# Schematic.net
KiCad netlist of a schematic drawn in EAGLE
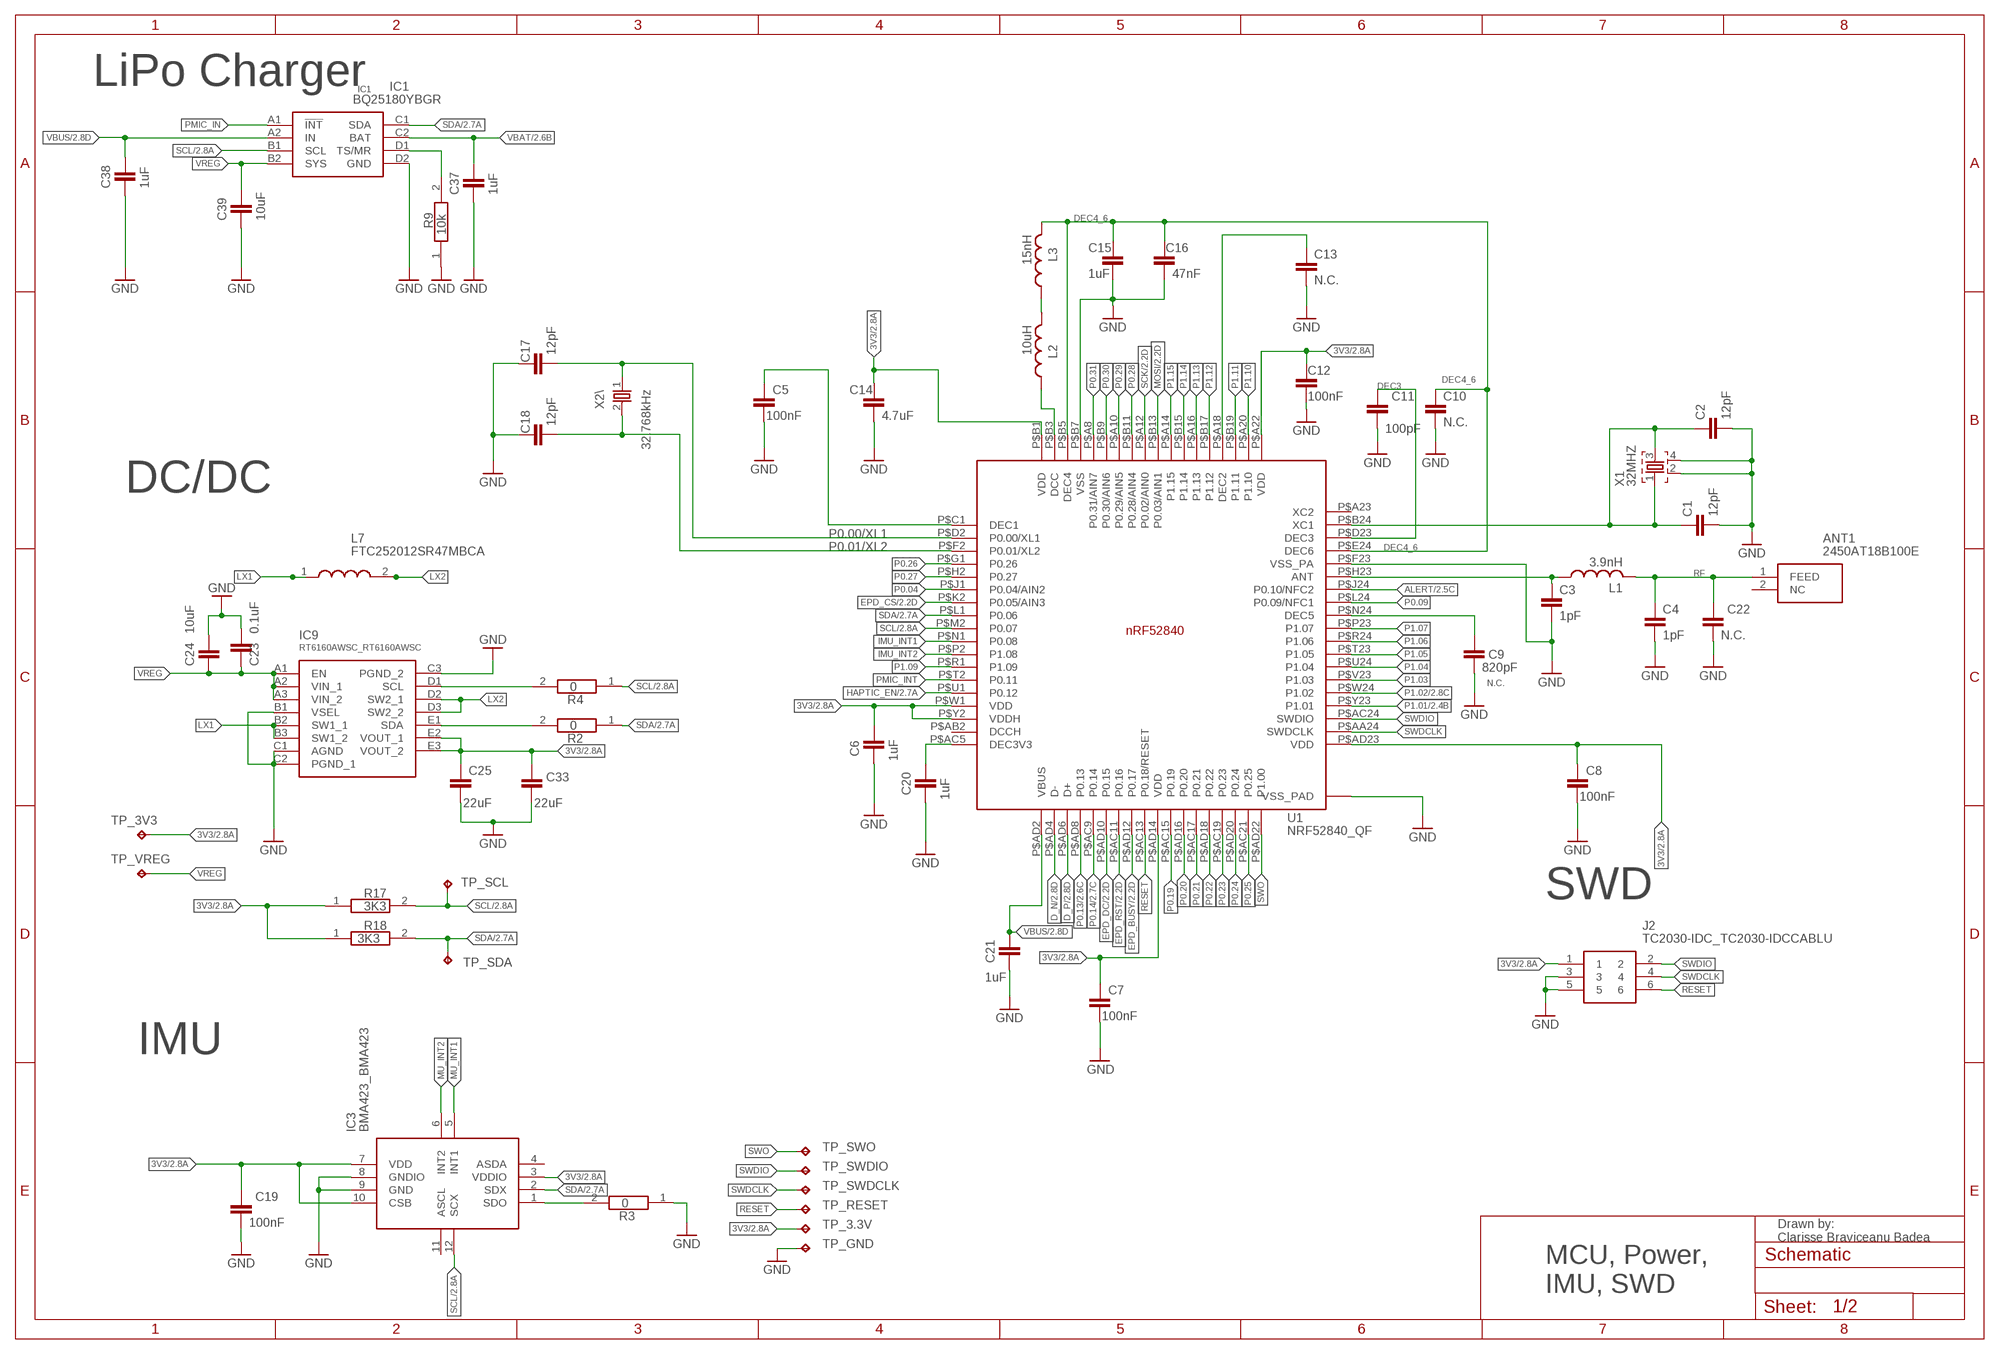
[diagram p0: schematic, sheet 1]
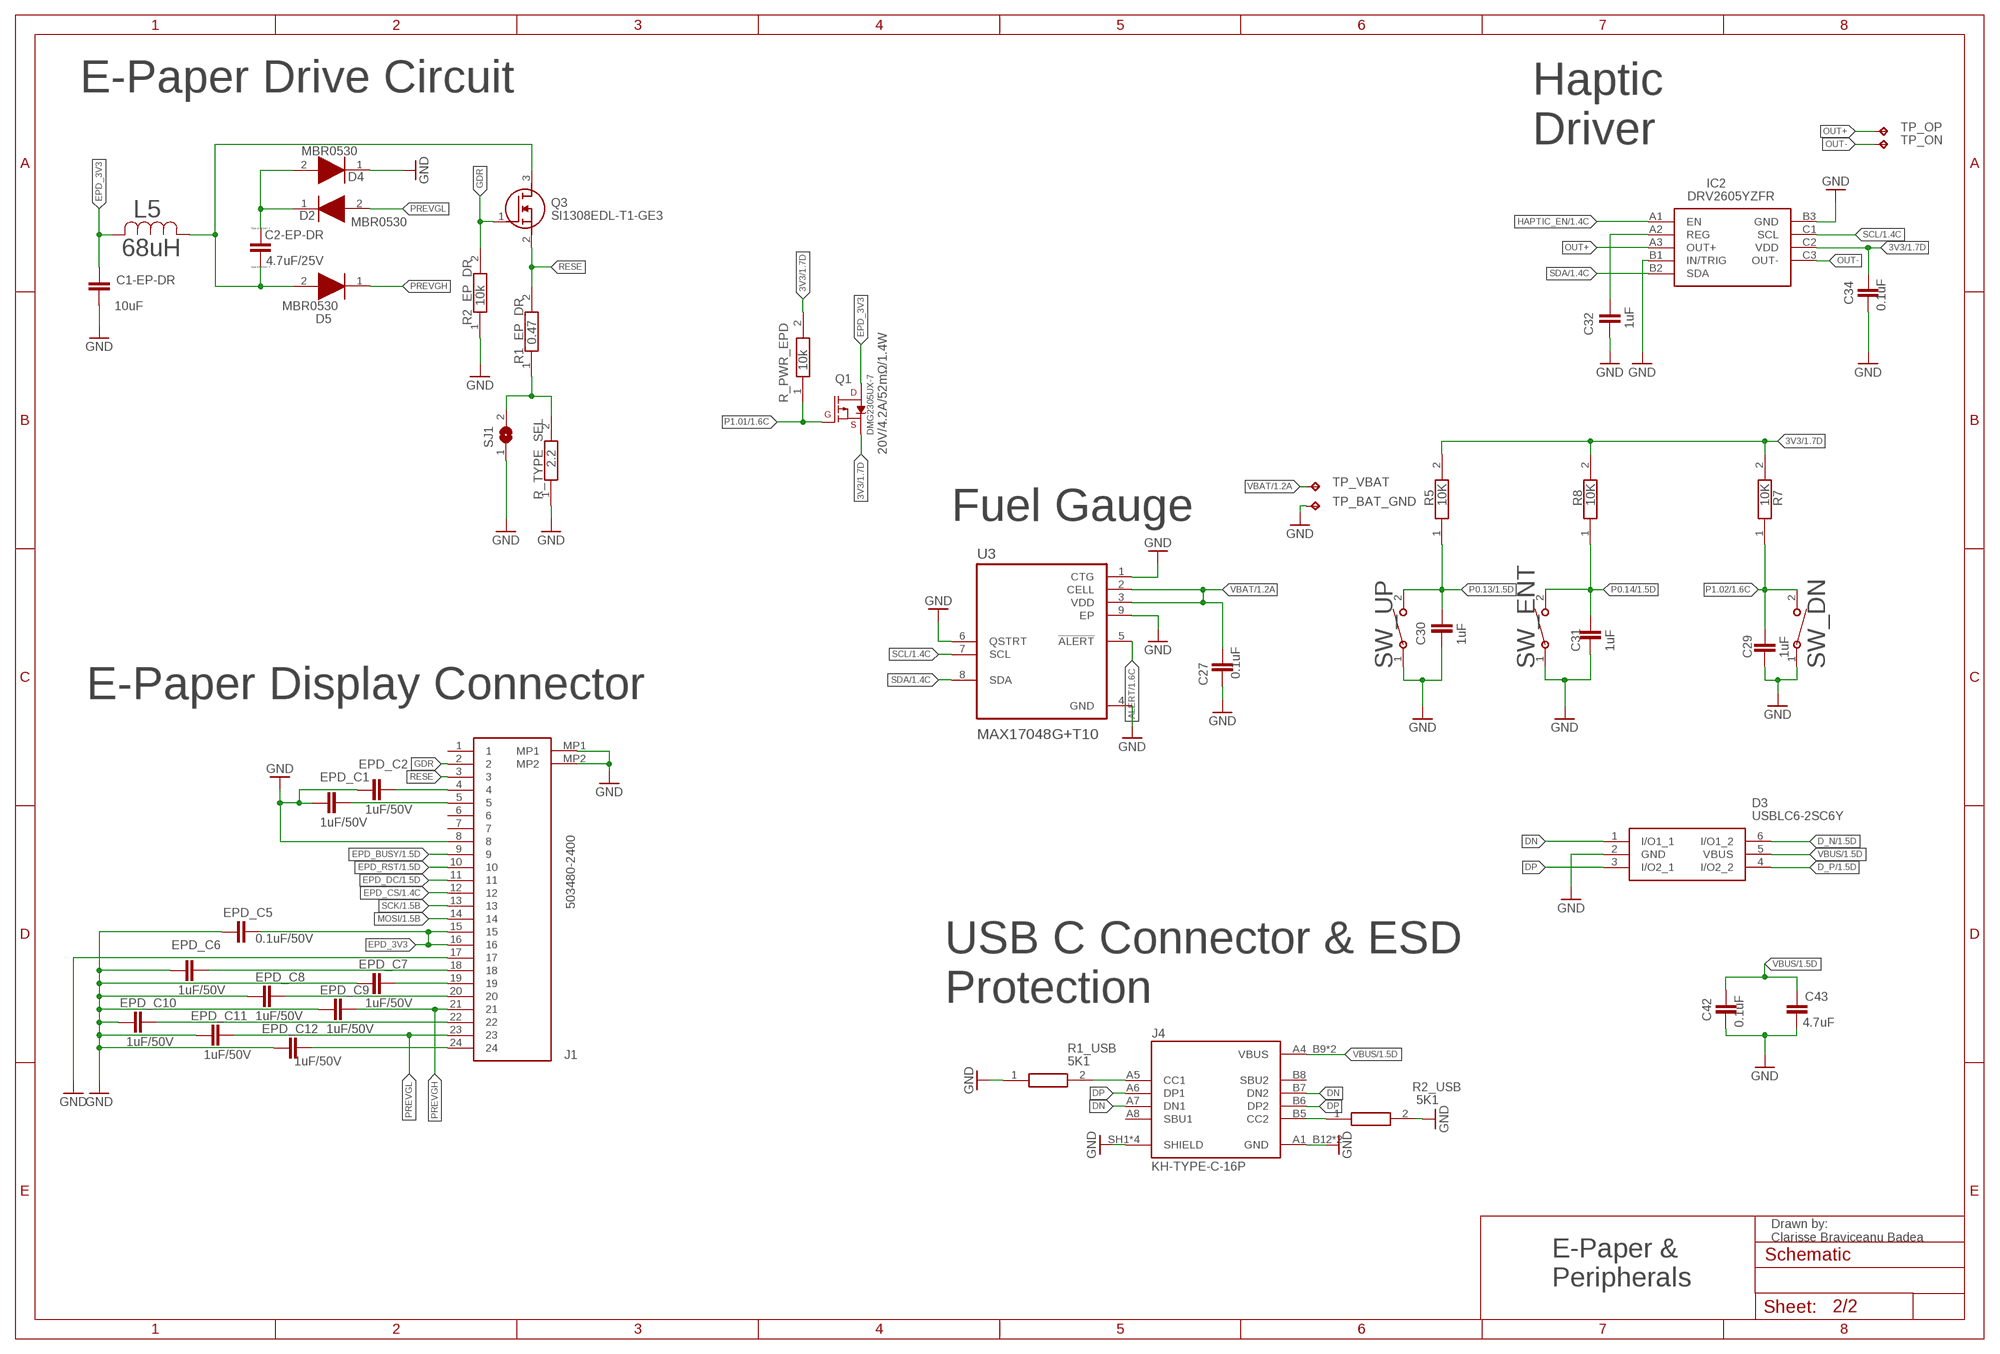
[diagram p1: schematic, sheet 2]

(export (version "E")
  (design (tool "Eeschema 10.0.6"))
  (components
    (comp (ref "ANT1")
      (value "2450AT18B100E")
      (footprint "eagle-import:2450AT18B100E_ANTC3216X140N")
      (fields (field (name "MOUSER_PART_NUMBER") "609-2450AT18B100E"))
      (libsource (lib "eagle-import") (part "2450AT18B100E_2450AT18B100E"))
    )
    (comp (ref "C1")
      (value "12pF")
      (footprint "eagle-import:NORDIC_NRF_3_RESC0201_N")
      (libsource (lib "eagle-import") (part "NORDIC_NRF_3_CAPACITOR_0201_N"))
    )
    (comp (ref "C2")
      (value "12pF")
      (footprint "eagle-import:NORDIC_NRF_3_RESC0201_N")
      (libsource (lib "eagle-import") (part "NORDIC_NRF_3_CAPACITOR_0201_N"))
    )
    (comp (ref "C3")
      (value "1pF")
      (footprint "eagle-import:NORDIC_NRF_3_RESC0201_N")
      (libsource (lib "eagle-import") (part "NORDIC_NRF_3_CAPACITOR_0201_N"))
    )
    (comp (ref "C4")
      (value "1pF")
      (footprint "eagle-import:NORDIC_NRF_3_RESC0201_N")
      (libsource (lib "eagle-import") (part "NORDIC_NRF_3_CAPACITOR_0201_N"))
    )
    (comp (ref "C5")
      (value "100nF")
      (footprint "eagle-import:NORDIC_NRF_3_RESC0201_N")
      (libsource (lib "eagle-import") (part "NORDIC_NRF_3_CAPACITOR_0201_N"))
    )
    (comp (ref "C6")
      (value "1uF")
      (footprint "eagle-import:NORDIC_NRF_3_RESC0402_N")
      (libsource (lib "eagle-import") (part "NORDIC_NRF_3_CAPACITOR_0402_N"))
    )
    (comp (ref "C7")
      (value "100nF")
      (footprint "eagle-import:NORDIC_NRF_3_RESC0201_N")
      (libsource (lib "eagle-import") (part "NORDIC_NRF_3_CAPACITOR_0201_N"))
    )
    (comp (ref "C8")
      (value "100nF")
      (footprint "eagle-import:NORDIC_NRF_3_RESC0201_N")
      (libsource (lib "eagle-import") (part "NORDIC_NRF_3_CAPACITOR_0201_N"))
    )
    (comp (ref "C9")
      (value "820pF")
      (footprint "eagle-import:NORDIC_NRF_3_RESC0201_N")
      (libsource (lib "eagle-import") (part "NORDIC_NRF_3_CAPACITOR_0201_N"))
    )
    (comp (ref "C10")
      (value "N.C.")
      (footprint "eagle-import:NORDIC_NRF_3_RESC0201_N")
      (libsource (lib "eagle-import") (part "NORDIC_NRF_3_CAPACITOR_0201_N"))
    )
    (comp (ref "C11")
      (value "100pF")
      (footprint "eagle-import:NORDIC_NRF_3_RESC0201_N")
      (libsource (lib "eagle-import") (part "NORDIC_NRF_3_CAPACITOR_0201_N"))
    )
    (comp (ref "C12")
      (value "100nF")
      (footprint "eagle-import:NORDIC_NRF_3_RESC0201_N")
      (libsource (lib "eagle-import") (part "NORDIC_NRF_3_CAPACITOR_0201_N"))
    )
    (comp (ref "C13")
      (value "N.C.")
      (footprint "eagle-import:NORDIC_NRF_3_RESC0201_N")
      (libsource (lib "eagle-import") (part "NORDIC_NRF_3_CAPACITOR_0201_N"))
    )
    (comp (ref "C14")
      (value "4.7uF")
      (footprint "eagle-import:NORDIC_NRF_3_RESC0402_N")
      (libsource (lib "eagle-import") (part "NORDIC_NRF_3_CAPACITOR_0402_N"))
    )
    (comp (ref "C15")
      (value "1uF")
      (footprint "eagle-import:NORDIC_NRF_3_RESC0402_N")
      (libsource (lib "eagle-import") (part "NORDIC_NRF_3_CAPACITOR_0402_N"))
    )
    (comp (ref "C16")
      (value "47nF")
      (footprint "eagle-import:NORDIC_NRF_3_RESC0201_N")
      (libsource (lib "eagle-import") (part "NORDIC_NRF_3_CAPACITOR_0201_N"))
    )
    (comp (ref "C17")
      (value "12pF")
      (footprint "eagle-import:NORDIC_NRF_3_RESC0201_N")
      (libsource (lib "eagle-import") (part "NORDIC_NRF_3_CAPACITOR_0201_N"))
    )
    (comp (ref "C18")
      (value "12pF")
      (footprint "eagle-import:NORDIC_NRF_3_RESC0201_N")
      (libsource (lib "eagle-import") (part "NORDIC_NRF_3_CAPACITOR_0201_N"))
    )
    (comp (ref "C19")
      (value "100nF")
      (footprint "eagle-import:NORDIC_NRF_3_RESC0201_N")
      (libsource (lib "eagle-import") (part "NORDIC_NRF_3_CAPACITOR_0201_N"))
    )
    (comp (ref "C20")
      (value "1uF")
      (footprint "eagle-import:NORDIC_NRF_3_RESC0402_N")
      (libsource (lib "eagle-import") (part "NORDIC_NRF_3_CAPACITOR_0402_N"))
    )
    (comp (ref "C21")
      (value "1uF")
      (footprint "eagle-import:NORDIC_NRF_3_RESC0402_N")
      (libsource (lib "eagle-import") (part "NORDIC_NRF_3_CAPACITOR_0402_N"))
    )
    (comp (ref "C22")
      (value "N.C.")
      (footprint "eagle-import:NORDIC_NRF_3_RESC0201_N")
      (libsource (lib "eagle-import") (part "NORDIC_NRF_3_CAPACITOR_0201_N"))
    )
    (comp (ref "C23")
      (value "0.1uF")
      (footprint "eagle-import:NORDIC_NRF_3_RESC0201_N")
      (libsource (lib "eagle-import") (part "NORDIC_NRF_3_CAPACITOR_0201_N"))
    )
    (comp (ref "C24")
      (value "10uF")
      (footprint "eagle-import:NORDIC_NRF_3_RESC0402_N")
      (libsource (lib "eagle-import") (part "NORDIC_NRF_3_CAPACITOR_0402_N"))
    )
    (comp (ref "C25")
      (value "22uF")
      (footprint "eagle-import:NORDIC_NRF_3_RESC0402_N")
      (libsource (lib "eagle-import") (part "NORDIC_NRF_3_CAPACITOR_0402_N"))
    )
    (comp (ref "C33")
      (value "22uF")
      (footprint "eagle-import:NORDIC_NRF_3_RESC0402_N")
      (libsource (lib "eagle-import") (part "NORDIC_NRF_3_CAPACITOR_0402_N"))
    )
    (comp (ref "C37")
      (value "1uF")
      (footprint "eagle-import:NORDIC_NRF_3_RESC0402_N")
      (libsource (lib "eagle-import") (part "NORDIC_NRF_3_CAPACITOR_0402_N"))
    )
    (comp (ref "C38")
      (value "1uF")
      (footprint "eagle-import:NORDIC_NRF_3_RESC0402_N")
      (libsource (lib "eagle-import") (part "NORDIC_NRF_3_CAPACITOR_0402_N"))
    )
    (comp (ref "C39")
      (value "10uF")
      (footprint "eagle-import:NORDIC_NRF_3_RESC0402_N")
      (libsource (lib "eagle-import") (part "NORDIC_NRF_3_CAPACITOR_0402_N"))
    )
    (comp (ref "IC1")
      (value "BQ25180YBGR")
      (footprint "eagle-import:BQ25180YBGR_BGA8C40P2X4_100X155X50")
      (fields (field (name "MOUSER_PART_NUMBER") "595-BQ25180YBGR"))
      (libsource (lib "eagle-import") (part "BQ25180YBGR_BQ25180YBGR"))
    )
    (comp (ref "IC3")
      (value "BMA423_BMA423")
      (footprint "eagle-import:BMA423_BMA423")
      (fields
        (field (name "MANUFACTURER_PART_NUMBER") "BMA423")
        (field (name "MOUSER_PART_NUMBER") "262-BMA423")
      )
      (libsource (lib "eagle-import") (part "BMA423_BMA423"))
    )
    (comp (ref "IC9")
      (value "RT6160AWSC_RT6160AWSC")
      (footprint "eagle-import:RT6160AWSC_BGA15C40P3X5_140X230X60")
      (fields
        (field (name "MANUFACTURER_PART_NUMBER") "RT6160AWSC")
        (field (name "MOUSER_PART_NUMBER") "835-RT6160AWSC")
      )
      (libsource (lib "eagle-import") (part "RT6160AWSC_RT6160AWSC"))
    )
    (comp (ref "J2")
      (value "TC2030-IDC_TC2030-IDCCABLU")
      (footprint "eagle-import:TC2030-IDC_TC2030IDC")
      (libsource (lib "eagle-import") (part "TC2030-IDC_TC2030-IDCCABLU"))
    )
    (comp (ref "L1")
      (value "3.9nH")
      (footprint "eagle-import:NORDIC_NRF_2_RESC0402_L")
      (libsource (lib "eagle-import") (part "NORDIC_NRF_2_INDUCTOR_0402_L"))
    )
    (comp (ref "L2")
      (value "10uH")
      (footprint "eagle-import:NORDIC_NRF_2_RESC0402_L")
      (libsource (lib "eagle-import") (part "NORDIC_NRF_2_INDUCTOR_0402_L"))
    )
    (comp (ref "L3")
      (value "15nH")
      (footprint "eagle-import:NORDIC_NRF_2_RESC0402_L")
      (libsource (lib "eagle-import") (part "NORDIC_NRF_2_INDUCTOR_0402_L"))
    )
    (comp (ref "L7")
      (value "FTC252012SR47MBCA")
      (footprint "eagle-import:MLP2016SR47MT0S1_INDC2016X100N")
      (libsource (lib "eagle-import") (part "MLP2016SR47MT0S1_FTC252012SR47MBCA"))
    )
    (comp (ref "R2")
      (value "0")
      (footprint "eagle-import:CPF0201D7K68C1_0201")
      (libsource (lib "eagle-import") (part "CPF0201D7K68C1_CPF0201D7K68C1"))
    )
    (comp (ref "R3")
      (value "0")
      (footprint "eagle-import:CPF0201D7K68C1_0201")
      (libsource (lib "eagle-import") (part "CPF0201D7K68C1_CPF0201D7K68C1"))
    )
    (comp (ref "R4")
      (value "0")
      (footprint "eagle-import:CPF0201D7K68C1_0201")
      (libsource (lib "eagle-import") (part "CPF0201D7K68C1_CPF0201D7K68C1"))
    )
    (comp (ref "R9")
      (value "10k")
      (footprint "eagle-import:CPF0201D7K68C1_0201")
      (libsource (lib "eagle-import") (part "CPF0201D7K68C1_CPF0201D7K68C1"))
    )
    (comp (ref "R17")
      (value "3K3")
      (footprint "eagle-import:CPF0201D7K68C1_0201")
      (libsource (lib "eagle-import") (part "CPF0201D7K68C1_CPF0201D7K68C1"))
    )
    (comp (ref "R18")
      (value "3K3")
      (footprint "eagle-import:CPF0201D7K68C1_0201")
      (libsource (lib "eagle-import") (part "CPF0201D7K68C1_CPF0201D7K68C1"))
    )
    (comp (ref "TP_3.3V")
      (value "HECTOR_WATCH_1_TPTP20R")
      (footprint "eagle-import:HECTOR_WATCH_1_TP20R")
      (libsource (lib "eagle-import") (part "HECTOR_WATCH_1_TPTP20R"))
    )
    (comp (ref "TP_3V3")
      (value "HECTOR_WATCH_1_TPTP20R")
      (footprint "eagle-import:HECTOR_WATCH_1_TP20R")
      (libsource (lib "eagle-import") (part "HECTOR_WATCH_1_TPTP20R"))
    )
    (comp (ref "TP_GND")
      (value "HECTOR_WATCH_1_TPTP20R")
      (footprint "eagle-import:HECTOR_WATCH_1_TP20R")
      (libsource (lib "eagle-import") (part "HECTOR_WATCH_1_TPTP20R"))
    )
    (comp (ref "TP_RESET")
      (value "HECTOR_WATCH_1_TPTP20R")
      (footprint "eagle-import:HECTOR_WATCH_1_TP20R")
      (libsource (lib "eagle-import") (part "HECTOR_WATCH_1_TPTP20R"))
    )
    (comp (ref "TP_SCL")
      (value "HECTOR_WATCH_1_TPTP20R")
      (footprint "eagle-import:HECTOR_WATCH_1_TP20R")
      (libsource (lib "eagle-import") (part "HECTOR_WATCH_1_TPTP20R"))
    )
    (comp (ref "TP_SDA")
      (value "HECTOR_WATCH_1_TPTP20R")
      (footprint "eagle-import:HECTOR_WATCH_1_TP20R")
      (libsource (lib "eagle-import") (part "HECTOR_WATCH_1_TPTP20R"))
    )
    (comp (ref "TP_SWDCLK")
      (value "HECTOR_WATCH_1_TPTP20R")
      (footprint "eagle-import:HECTOR_WATCH_1_TP20R")
      (libsource (lib "eagle-import") (part "HECTOR_WATCH_1_TPTP20R"))
    )
    (comp (ref "TP_SWDIO")
      (value "HECTOR_WATCH_1_TPTP20R")
      (footprint "eagle-import:HECTOR_WATCH_1_TP20R")
      (libsource (lib "eagle-import") (part "HECTOR_WATCH_1_TPTP20R"))
    )
    (comp (ref "TP_SWO")
      (value "HECTOR_WATCH_1_TPTP20R")
      (footprint "eagle-import:HECTOR_WATCH_1_TP20R")
      (libsource (lib "eagle-import") (part "HECTOR_WATCH_1_TPTP20R"))
    )
    (comp (ref "TP_VREG")
      (value "HECTOR_WATCH_1_TPTP20R")
      (footprint "eagle-import:HECTOR_WATCH_1_TP20R")
      (libsource (lib "eagle-import") (part "HECTOR_WATCH_1_TPTP20R"))
    )
    (comp (ref "U1")
      (value "NRF52840_QF")
      (footprint "eagle-import:NORDIC_NRF_4_AQFN50P700X700X85_HS-74N")
      (libsource (lib "eagle-import") (part "NORDIC_NRF_4_NRF52840_QF"))
    )
    (comp (ref "X1")
      (value "32MHZ")
      (footprint "eagle-import:NORDIC_NRF_BT-XTAL_2016_N")
      (libsource (lib "eagle-import") (part "NORDIC_NRF_XTAL_32MHZ"))
    )
    (comp (ref "X2\\")
      (value "32.768kHz")
      (footprint "eagle-import:NORDIC_NRF_1_XTAL_3215_N")
      (libsource (lib "eagle-import") (part "NORDIC_NRF_1_XTAL_32KHZ"))
    )
    (comp (ref "C1-EP-DR")
      (value "10uF")
      (footprint "eagle-import:NORDIC_NRF_3_RESC0402_N")
      (libsource (lib "eagle-import") (part "NORDIC_NRF_3_CAPACITOR_0402_N"))
    )
    (comp (ref "C2-EP-DR")
      (value "4.7uF/25V")
      (footprint "eagle-import:ESP32_C6_LIBRARY_1_ESP32_WROVER_EAGLE-LTSPICE_C0402")
      (libsource (lib "eagle-import") (part "ESP32_C6_LIBRARY_1_ESP32_WROVER_EAGLE-LTSPICE_CC0402"))
    )
    (comp (ref "C27")
      (value "0.1uF")
      (footprint "eagle-import:NORDIC_NRF_3_RESC0402_N")
      (libsource (lib "eagle-import") (part "NORDIC_NRF_3_CAPACITOR_0402_N"))
    )
    (comp (ref "C29")
      (value "1uF")
      (footprint "eagle-import:NORDIC_NRF_3_RESC0402_N")
      (libsource (lib "eagle-import") (part "NORDIC_NRF_3_CAPACITOR_0402_N"))
    )
    (comp (ref "C30")
      (value "1uF")
      (footprint "eagle-import:NORDIC_NRF_3_RESC0402_N")
      (libsource (lib "eagle-import") (part "NORDIC_NRF_3_CAPACITOR_0402_N"))
    )
    (comp (ref "C31")
      (value "1uF")
      (footprint "eagle-import:NORDIC_NRF_3_RESC0402_N")
      (libsource (lib "eagle-import") (part "NORDIC_NRF_3_CAPACITOR_0402_N"))
    )
    (comp (ref "C32")
      (value "1uF")
      (footprint "eagle-import:NORDIC_NRF_3_RESC0402_N")
      (libsource (lib "eagle-import") (part "NORDIC_NRF_3_CAPACITOR_0402_N"))
    )
    (comp (ref "C34")
      (value "0.1uF")
      (footprint "eagle-import:NORDIC_NRF_3_RESC0201_N")
      (libsource (lib "eagle-import") (part "NORDIC_NRF_3_CAPACITOR_0201_N"))
    )
    (comp (ref "C42")
      (value "0.1uF")
      (footprint "eagle-import:NORDIC_NRF_3_RESC0201_N")
      (libsource (lib "eagle-import") (part "NORDIC_NRF_3_CAPACITOR_0201_N"))
    )
    (comp (ref "C43")
      (value "4.7uF")
      (footprint "eagle-import:NORDIC_NRF_3_RESC0402_N")
      (libsource (lib "eagle-import") (part "NORDIC_NRF_3_CAPACITOR_0402_N"))
    )
    (comp (ref "D2")
      (value "MBR0530")
      (footprint "eagle-import:ESP32_C6_LIBRARY_5_SOD3716X135N")
      (fields (field (name "MF") "ON Semiconductor"))
      (libsource (lib "eagle-import") (part "ESP32_C6_LIBRARY_5_MBR0530"))
    )
    (comp (ref "D3")
      (value "USBLC6-2SC6Y")
      (footprint "eagle-import:ESP32_C6_LIBRARY_3_SOT95P280X145-6N")
      (fields (field (name "MF") "STMicroelectronics"))
      (libsource (lib "eagle-import") (part "ESP32_C6_LIBRARY_3_USBLC6-2SC6Y"))
    )
    (comp (ref "D4")
      (value "MBR0530")
      (footprint "eagle-import:ESP32_C6_LIBRARY_5_SOD3716X135N")
      (fields (field (name "MF") "ON Semiconductor"))
      (libsource (lib "eagle-import") (part "ESP32_C6_LIBRARY_5_MBR0530"))
    )
    (comp (ref "D5")
      (value "MBR0530")
      (footprint "eagle-import:ESP32_C6_LIBRARY_5_SOD3716X135N")
      (fields (field (name "MF") "ON Semiconductor"))
      (libsource (lib "eagle-import") (part "ESP32_C6_LIBRARY_5_MBR0530"))
    )
    (comp (ref "EPD_C1")
      (value "1uF/50V")
      (footprint "eagle-import:NORDIC_NRF_3_RESC0402_N")
      (libsource (lib "eagle-import") (part "NORDIC_NRF_3_CAPACITOR_0402_N"))
    )
    (comp (ref "EPD_C2")
      (value "1uF/50V")
      (footprint "eagle-import:NORDIC_NRF_3_RESC0402_N")
      (libsource (lib "eagle-import") (part "NORDIC_NRF_3_CAPACITOR_0402_N"))
    )
    (comp (ref "EPD_C5")
      (value "0.1uF/50V")
      (footprint "eagle-import:NORDIC_NRF_3_RESC0402_N")
      (libsource (lib "eagle-import") (part "NORDIC_NRF_3_CAPACITOR_0402_N"))
    )
    (comp (ref "EPD_C6")
      (value "1uF/50V")
      (footprint "eagle-import:NORDIC_NRF_3_RESC0402_N")
      (libsource (lib "eagle-import") (part "NORDIC_NRF_3_CAPACITOR_0402_N"))
    )
    (comp (ref "EPD_C7")
      (value "1uF/50V")
      (footprint "eagle-import:NORDIC_NRF_3_RESC0402_N")
      (libsource (lib "eagle-import") (part "NORDIC_NRF_3_CAPACITOR_0402_N"))
    )
    (comp (ref "EPD_C8")
      (value "1uF/50V")
      (footprint "eagle-import:NORDIC_NRF_3_RESC0402_N")
      (libsource (lib "eagle-import") (part "NORDIC_NRF_3_CAPACITOR_0402_N"))
    )
    (comp (ref "EPD_C9")
      (value "1uF/50V")
      (footprint "eagle-import:NORDIC_NRF_3_RESC0402_N")
      (libsource (lib "eagle-import") (part "NORDIC_NRF_3_CAPACITOR_0402_N"))
    )
    (comp (ref "EPD_C10")
      (value "1uF/50V")
      (footprint "eagle-import:NORDIC_NRF_3_RESC0402_N")
      (libsource (lib "eagle-import") (part "NORDIC_NRF_3_CAPACITOR_0402_N"))
    )
    (comp (ref "EPD_C11")
      (value "1uF/50V")
      (footprint "eagle-import:NORDIC_NRF_3_RESC0402_N")
      (libsource (lib "eagle-import") (part "NORDIC_NRF_3_CAPACITOR_0402_N"))
    )
    (comp (ref "EPD_C12")
      (value "1uF/50V")
      (footprint "eagle-import:NORDIC_NRF_3_RESC0402_N")
      (libsource (lib "eagle-import") (part "NORDIC_NRF_3_CAPACITOR_0402_N"))
    )
    (comp (ref "IC2")
      (value "DRV2605YZFR")
      (footprint "eagle-import:DRV2605YZFR_BGA9C50P3X3_144X144X62")
      (libsource (lib "eagle-import") (part "DRV2605YZFR_DRV2605YZFR"))
    )
    (comp (ref "J1")
      (value "503480-2400")
      (footprint "eagle-import:503480-2400_5034802400")
      (fields (field (name "MOUSER_PART_NUMBER") "538-503480-2400"))
      (libsource (lib "eagle-import") (part "503480-2400_503480-2400"))
    )
    (comp (ref "J4")
      (value "KH-TYPE-C-16P")
      (footprint "eagle-import:KH-TYPE-C-16P_KINGHELM_KH-TYPE-C-16P")
      (fields (field (name "MF") "kinghelm"))
      (libsource (lib "eagle-import") (part "KH-TYPE-C-16P_KH-TYPE-C-16P"))
    )
    (comp (ref "L5")
      (value "68uH")
      (footprint "eagle-import:ESP32_C6_LIBRARY_2_IND_4828-WE-TPC_WRE")
      (fields
        (field (name "MANUFACTURER_PART_NUMBER") "744043680")
        (field (name "COPYRIGHT") "Copyright (C) 2024 Ultra Librarian. All rights reserved.")
      )
      (libsource (lib "eagle-import") (part "ESP32_C6_LIBRARY_2_744043680IND_4828-WE-TPC_WRE"))
    )
    (comp (ref "Q1")
      (value "20V/4.2A/52mΩ/1.4W")
      (footprint "eagle-import:ESP32_C6_LIBRARY_4_ESP32_C6_LIBRARY_4_ESP32_C6_LIBRARY_4_ESP32_C6_LIBRARY_4_ESP32_WROVER_SPARKFUN-DISCRETESEMI_SOT23-3")
      (libsource (lib "eagle-import") (part "ESP32_C6_LIBRARY_4_ESP32_WROVER_SPARKFUN-DISCRETESEMI_MOSFET_PCH-DMG2305UX-7"))
    )
    (comp (ref "Q3")
      (value "SI1308EDL-T1-GE3")
      (footprint "eagle-import:ESP32_C6_LIBRARY_6_SOT65P210X110-3N")
      (fields (field (name "MF") "Vishay Siliconix"))
      (libsource (lib "eagle-import") (part "ESP32_C6_LIBRARY_6_SI1308EDL-T1-GE3"))
    )
    (comp (ref "R1_EP_DR")
      (value "0.47")
      (footprint "eagle-import:CPF0201D7K68C1_0201")
      (libsource (lib "eagle-import") (part "CPF0201D7K68C1_CPF0201D7K68C1"))
    )
    (comp (ref "R1_USB")
      (value "5K1")
      (footprint "eagle-import:CPF0201D7K68C1_0201")
      (libsource (lib "eagle-import") (part "CPF0201D7K68C1_CPF0201D7K68C1"))
    )
    (comp (ref "R2_EP_DR")
      (value "10k")
      (footprint "eagle-import:CPF0201D7K68C1_0201")
      (libsource (lib "eagle-import") (part "CPF0201D7K68C1_CPF0201D7K68C1"))
    )
    (comp (ref "R2_USB")
      (value "5K1")
      (footprint "eagle-import:CPF0201D7K68C1_0201")
      (libsource (lib "eagle-import") (part "CPF0201D7K68C1_CPF0201D7K68C1"))
    )
    (comp (ref "R5")
      (value "10K")
      (footprint "eagle-import:CPF0201D7K68C1_0201")
      (libsource (lib "eagle-import") (part "CPF0201D7K68C1_CPF0201D7K68C1"))
    )
    (comp (ref "R7")
      (value "10K")
      (footprint "eagle-import:CPF0201D7K68C1_0201")
      (libsource (lib "eagle-import") (part "CPF0201D7K68C1_CPF0201D7K68C1"))
    )
    (comp (ref "R8")
      (value "10K")
      (footprint "eagle-import:CPF0201D7K68C1_0201")
      (libsource (lib "eagle-import") (part "CPF0201D7K68C1_CPF0201D7K68C1"))
    )
    (comp (ref "R_PWR_EPD")
      (value "10k")
      (footprint "eagle-import:CPF0201D7K68C1_0201")
      (libsource (lib "eagle-import") (part "CPF0201D7K68C1_CPF0201D7K68C1"))
    )
    (comp (ref "R_TYPE_SEL")
      (value "2.2")
      (footprint "eagle-import:CPF0201D7K68C1_0201")
      (libsource (lib "eagle-import") (part "CPF0201D7K68C1_CPF0201D7K68C1"))
    )
    (comp (ref "SJ1")
      (value "ESP32_C6_LIBRARY_7_JUMPER_SJ")
      (footprint "eagle-import:ESP32_C6_LIBRARY_7_JUMPER_SJ")
      (libsource (lib "eagle-import") (part "ESP32_C6_LIBRARY_7_JUMPER_SJ"))
    )
    (comp (ref "SW_DN")
      (value "2025-10-22_07-23-44_LIBRARY_EVP-AKE31ASW_EVP-AKE31A_PAN")
      (footprint "eagle-import:2025-10-22_07-23-44_LIBRARY_SW_EVP-AKE31A_PAN")
      (libsource (lib "eagle-import") (part "2025-10-22_07-23-44_LIBRARY_EVP-AKE31ASW_EVP-AKE31A_PAN"))
    )
    (comp (ref "SW_ENT")
      (value "2025-10-22_07-23-44_LIBRARY_EVP-AKE31ASW_EVP-AKE31A_PAN")
      (footprint "eagle-import:2025-10-22_07-23-44_LIBRARY_SW_EVP-AKE31A_PAN")
      (libsource (lib "eagle-import") (part "2025-10-22_07-23-44_LIBRARY_EVP-AKE31ASW_EVP-AKE31A_PAN"))
    )
    (comp (ref "SW_UP")
      (value "2025-10-22_07-23-44_LIBRARY_EVP-AKE31ASW_EVP-AKE31A_PAN")
      (footprint "eagle-import:2025-10-22_07-23-44_LIBRARY_SW_EVP-AKE31A_PAN")
      (libsource (lib "eagle-import") (part "2025-10-22_07-23-44_LIBRARY_EVP-AKE31ASW_EVP-AKE31A_PAN"))
    )
    (comp (ref "TP_BAT_GND")
      (value "HECTOR_WATCH_1_TPTP20R")
      (footprint "eagle-import:HECTOR_WATCH_1_TP20R")
      (libsource (lib "eagle-import") (part "HECTOR_WATCH_1_TPTP20R"))
    )
    (comp (ref "TP_ON")
      (value "HECTOR_WATCH_1_TPTP20R")
      (footprint "eagle-import:HECTOR_WATCH_1_TP20R")
      (libsource (lib "eagle-import") (part "HECTOR_WATCH_1_TPTP20R"))
    )
    (comp (ref "TP_OP")
      (value "HECTOR_WATCH_1_TPTP20R")
      (footprint "eagle-import:HECTOR_WATCH_1_TP20R")
      (libsource (lib "eagle-import") (part "HECTOR_WATCH_1_TPTP20R"))
    )
    (comp (ref "TP_VBAT")
      (value "HECTOR_WATCH_1_TPTP20R")
      (footprint "eagle-import:HECTOR_WATCH_1_TP20R")
      (libsource (lib "eagle-import") (part "HECTOR_WATCH_1_TPTP20R"))
    )
    (comp (ref "U3")
      (value "MAX17048G+T10")
      (footprint "eagle-import:ESP32_C6_LIBRARY_SON50P200X200X80-9N")
      (libsource (lib "eagle-import") (part "ESP32_C6_LIBRARY_MAX17048G+T10CC"))
    )
  )
  (nets
    (net (code "1") (name "3V3") (class "Default")
      (node (ref "C12") (pin "2") (pinfunction "2_2") (pintype "passive"))
      (node (ref "C14") (pin "1") (pinfunction "1_1") (pintype "passive"))
      (node (ref "C19") (pin "2") (pinfunction "2_2") (pintype "passive"))
      (node (ref "C25") (pin "1") (pinfunction "1_1") (pintype "passive"))
      (node (ref "C33") (pin "1") (pinfunction "1_1") (pintype "passive"))
      (node (ref "C34") (pin "1") (pinfunction "1_1") (pintype "passive"))
      (node (ref "C6") (pin "1") (pinfunction "1_1") (pintype "passive"))
      (node (ref "C7") (pin "1") (pinfunction "1_1") (pintype "passive"))
      (node (ref "C8") (pin "1") (pinfunction "1_1") (pintype "passive"))
      (node (ref "IC2") (pin "C2") (pinfunction "VDD_C2") (pintype "bidirectional"))
      (node (ref "IC3") (pin "10") (pinfunction "CSB_10") (pintype "bidirectional"))
      (node (ref "IC3") (pin "3") (pinfunction "VDDIO_3") (pintype "bidirectional"))
      (node (ref "IC3") (pin "7") (pinfunction "VDD_7") (pintype "bidirectional"))
      (node (ref "IC9") (pin "E2") (pinfunction "VOUT_1_E2") (pintype "bidirectional"))
      (node (ref "IC9") (pin "E3") (pinfunction "VOUT_2_E3") (pintype "bidirectional"))
      (node (ref "J2") (pin "1") (pinfunction "1_1") (pintype "bidirectional"))
      (node (ref "Q1") (pin "2") (pinfunction "S_2") (pintype "bidirectional"))
      (node (ref "R17") (pin "1") (pinfunction "1_1") (pintype "bidirectional"))
      (node (ref "R18") (pin "1") (pinfunction "1_1") (pintype "bidirectional"))
      (node (ref "R5") (pin "2") (pinfunction "2_2") (pintype "bidirectional"))
      (node (ref "R7") (pin "2") (pinfunction "2_2") (pintype "bidirectional"))
      (node (ref "R8") (pin "2") (pinfunction "2_2") (pintype "bidirectional"))
      (node (ref "R_PWR_EPD") (pin "2") (pinfunction "2_2") (pintype "bidirectional"))
      (node (ref "TP_3.3V") (pin "TP") (pinfunction "TP_TP") (pintype "input"))
      (node (ref "TP_3V3") (pin "TP") (pinfunction "TP_TP") (pintype "input"))
      (node (ref "U1") (pin "P$A22") (pinfunction "VDD_P$A22") (pintype "power_in"))
      (node (ref "U1") (pin "P$AD14") (pinfunction "VDD_P$AD14") (pintype "power_in"))
      (node (ref "U1") (pin "P$AD23") (pinfunction "VDD_P$AD23") (pintype "power_in"))
      (node (ref "U1") (pin "P$B1") (pinfunction "VDD_P$B1") (pintype "power_in"))
      (node (ref "U1") (pin "P$W1") (pinfunction "VDD_P$W1") (pintype "power_in"))
      (node (ref "U1") (pin "P$Y2") (pinfunction "VDDH_P$Y2") (pintype "power_in"))
    )
    (net (code "2") (name "ALERT") (class "Default")
      (node (ref "U1") (pin "P$J24") (pinfunction "P0.10/NFC2_P$J24") (pintype "bidirectional"))
      (node (ref "U3") (pin "5") (pinfunction "~{ALERT}_5") (pintype "output"))
    )
    (net (code "3") (name "DN") (class "Default")
      (node (ref "D3") (pin "1") (pinfunction "I/O1_1_1") (pintype "bidirectional"))
      (node (ref "J4") (pin "A7") (pinfunction "DN1_A7") (pintype "bidirectional"))
      (node (ref "J4") (pin "B7") (pinfunction "DN2_B7") (pintype "bidirectional"))
    )
    (net (code "4") (name "DP") (class "Default")
      (node (ref "D3") (pin "3") (pinfunction "I/O2_1_3") (pintype "bidirectional"))
      (node (ref "J4") (pin "A6") (pinfunction "DP1_A6") (pintype "bidirectional"))
      (node (ref "J4") (pin "B6") (pinfunction "DP2_B6") (pintype "bidirectional"))
    )
    (net (code "5") (name "D_N") (class "Default")
      (node (ref "D3") (pin "6") (pinfunction "I/O1_2_6") (pintype "bidirectional"))
      (node (ref "U1") (pin "P$AD4") (pinfunction "D-_P$AD4") (pintype "bidirectional"))
    )
    (net (code "6") (name "D_P") (class "Default")
      (node (ref "D3") (pin "4") (pinfunction "I/O2_2_4") (pintype "bidirectional"))
      (node (ref "U1") (pin "P$AD6") (pinfunction "D+_P$AD6") (pintype "bidirectional"))
    )
    (net (code "7") (name "EPD_3V3") (class "Default")
      (node (ref "C1-EP-DR") (pin "1") (pinfunction "1_1") (pintype "passive"))
      (node (ref "EPD_C5") (pin "2") (pinfunction "2_2") (pintype "passive"))
      (node (ref "J1") (pin "15") (pinfunction "15_15") (pintype "bidirectional"))
      (node (ref "J1") (pin "16") (pinfunction "16_16") (pintype "bidirectional"))
      (node (ref "L5") (pin "2") (pinfunction "2_2") (pintype "passive"))
      (node (ref "Q1") (pin "3") (pinfunction "D_3") (pintype "bidirectional"))
    )
    (net (code "8") (name "EPD_BUSY") (class "Default")
      (node (ref "J1") (pin "9") (pinfunction "9_9") (pintype "bidirectional"))
      (node (ref "U1") (pin "P$AD12") (pinfunction "P0.17_P$AD12") (pintype "bidirectional"))
    )
    (net (code "9") (name "EPD_CS") (class "Default")
      (node (ref "J1") (pin "12") (pinfunction "12_12") (pintype "bidirectional"))
      (node (ref "U1") (pin "P$K2") (pinfunction "P0.05/AIN3_P$K2") (pintype "bidirectional"))
    )
    (net (code "10") (name "EPD_DC") (class "Default")
      (node (ref "J1") (pin "11") (pinfunction "11_11") (pintype "bidirectional"))
      (node (ref "U1") (pin "P$AD10") (pinfunction "P0.15_P$AD10") (pintype "bidirectional"))
    )
    (net (code "11") (name "EPD_RST") (class "Default")
      (node (ref "J1") (pin "10") (pinfunction "10_10") (pintype "bidirectional"))
      (node (ref "U1") (pin "P$AC11") (pinfunction "P0.16_P$AC11") (pintype "bidirectional"))
    )
    (net (code "12") (name "GDR") (class "Default")
      (node (ref "J1") (pin "2") (pinfunction "2_2") (pintype "bidirectional"))
      (node (ref "Q3") (pin "1") (pinfunction "G_1") (pintype "bidirectional"))
      (node (ref "R2_EP_DR") (pin "2") (pinfunction "2_2") (pintype "bidirectional"))
    )
    (net (code "13") (name "GND") (class "Default")
      (node (ref "C1") (pin "2") (pinfunction "2_2") (pintype "passive"))
      (node (ref "C1-EP-DR") (pin "2") (pinfunction "2_2") (pintype "passive"))
      (node (ref "C10") (pin "1") (pinfunction "1_1") (pintype "passive"))
      (node (ref "C11") (pin "1") (pinfunction "1_1") (pintype "passive"))
      (node (ref "C12") (pin "1") (pinfunction "1_1") (pintype "passive"))
      (node (ref "C13") (pin "1") (pinfunction "1_1") (pintype "passive"))
      (node (ref "C14") (pin "2") (pinfunction "2_2") (pintype "passive"))
      (node (ref "C15") (pin "2") (pinfunction "2_2") (pintype "passive"))
      (node (ref "C16") (pin "1") (pinfunction "1_1") (pintype "passive"))
      (node (ref "C17") (pin "1") (pinfunction "1_1") (pintype "passive"))
      (node (ref "C18") (pin "1") (pinfunction "1_1") (pintype "passive"))
      (node (ref "C19") (pin "1") (pinfunction "1_1") (pintype "passive"))
      (node (ref "C2") (pin "2") (pinfunction "2_2") (pintype "passive"))
      (node (ref "C20") (pin "2") (pinfunction "2_2") (pintype "passive"))
      (node (ref "C21") (pin "2") (pinfunction "2_2") (pintype "passive"))
      (node (ref "C22") (pin "1") (pinfunction "1_1") (pintype "passive"))
      (node (ref "C23") (pin "1") (pinfunction "1_1") (pintype "passive"))
      (node (ref "C24") (pin "1") (pinfunction "1_1") (pintype "passive"))
      (node (ref "C25") (pin "2") (pinfunction "2_2") (pintype "passive"))
      (node (ref "C27") (pin "1") (pinfunction "1_1") (pintype "passive"))
      (node (ref "C29") (pin "2") (pinfunction "2_2") (pintype "passive"))
      (node (ref "C3") (pin "1") (pinfunction "1_1") (pintype "passive"))
      (node (ref "C30") (pin "1") (pinfunction "1_1") (pintype "passive"))
      (node (ref "C31") (pin "1") (pinfunction "1_1") (pintype "passive"))
      (node (ref "C32") (pin "1") (pinfunction "1_1") (pintype "passive"))
      (node (ref "C33") (pin "2") (pinfunction "2_2") (pintype "passive"))
      (node (ref "C34") (pin "2") (pinfunction "2_2") (pintype "passive"))
      (node (ref "C37") (pin "2") (pinfunction "2_2") (pintype "passive"))
      (node (ref "C38") (pin "2") (pinfunction "2_2") (pintype "passive"))
      (node (ref "C39") (pin "2") (pinfunction "2_2") (pintype "passive"))
      (node (ref "C4") (pin "1") (pinfunction "1_1") (pintype "passive"))
      (node (ref "C42") (pin "2") (pinfunction "2_2") (pintype "passive"))
      (node (ref "C43") (pin "2") (pinfunction "2_2") (pintype "passive"))
      (node (ref "C5") (pin "2") (pinfunction "2_2") (pintype "passive"))
      (node (ref "C6") (pin "2") (pinfunction "2_2") (pintype "passive"))
      (node (ref "C7") (pin "2") (pinfunction "2_2") (pintype "passive"))
      (node (ref "C8") (pin "2") (pinfunction "2_2") (pintype "passive"))
      (node (ref "C9") (pin "1") (pinfunction "1_1") (pintype "passive"))
      (node (ref "D3") (pin "2") (pinfunction "GND_2") (pintype "bidirectional"))
      (node (ref "D4") (pin "1") (pinfunction "K_1") (pintype "bidirectional"))
      (node (ref "EPD_C1") (pin "1") (pinfunction "1_1") (pintype "passive"))
      (node (ref "EPD_C10") (pin "1") (pinfunction "1_1") (pintype "passive"))
      (node (ref "EPD_C11") (pin "1") (pinfunction "1_1") (pintype "passive"))
      (node (ref "EPD_C12") (pin "1") (pinfunction "1_1") (pintype "passive"))
      (node (ref "EPD_C2") (pin "1") (pinfunction "1_1") (pintype "passive"))
      (node (ref "EPD_C5") (pin "1") (pinfunction "1_1") (pintype "passive"))
      (node (ref "EPD_C6") (pin "1") (pinfunction "1_1") (pintype "passive"))
      (node (ref "EPD_C7") (pin "1") (pinfunction "1_1") (pintype "passive"))
      (node (ref "EPD_C8") (pin "1") (pinfunction "1_1") (pintype "passive"))
      (node (ref "EPD_C9") (pin "1") (pinfunction "1_1") (pintype "passive"))
      (node (ref "IC1") (pin "D2") (pinfunction "GND_D2") (pintype "bidirectional"))
      (node (ref "IC2") (pin "B1") (pinfunction "IN/TRIG_B1") (pintype "bidirectional"))
      (node (ref "IC2") (pin "B3") (pinfunction "GND_B3") (pintype "bidirectional"))
      (node (ref "IC3") (pin "8") (pinfunction "GNDIO_8") (pintype "bidirectional"))
      (node (ref "IC3") (pin "9") (pinfunction "GND_9") (pintype "bidirectional"))
      (node (ref "IC9") (pin "B1") (pinfunction "VSEL_B1") (pintype "bidirectional"))
      (node (ref "IC9") (pin "C1") (pinfunction "AGND_C1") (pintype "bidirectional"))
      (node (ref "IC9") (pin "C2") (pinfunction "PGND_1_C2") (pintype "bidirectional"))
      (node (ref "IC9") (pin "C3") (pinfunction "PGND_2_C3") (pintype "bidirectional"))
      (node (ref "J1") (pin "17") (pinfunction "17_17") (pintype "bidirectional"))
      (node (ref "J1") (pin "8") (pinfunction "8_8") (pintype "bidirectional"))
      (node (ref "J1") (pin "MP1") (pinfunction "MP1_MP1") (pintype "bidirectional"))
      (node (ref "J1") (pin "MP2") (pinfunction "MP2_MP2") (pintype "bidirectional"))
      (node (ref "J2") (pin "3") (pinfunction "3_3") (pintype "bidirectional"))
      (node (ref "J2") (pin "5") (pinfunction "5_5") (pintype "bidirectional"))
      (node (ref "J4") (pin "A12_B1") (pinfunction "GND_A12_B1") (pintype "power_in"))
      (node (ref "J4") (pin "A1_B12") (pinfunction "GND_A1_B12") (pintype "power_in"))
      (node (ref "J4") (pin "SH1") (pinfunction "SHIELD_SH1") (pintype "passive"))
      (node (ref "J4") (pin "SH2") (pinfunction "SHIELD_SH2") (pintype "passive"))
      (node (ref "J4") (pin "SH3") (pinfunction "SHIELD_SH3") (pintype "passive"))
      (node (ref "J4") (pin "SH4") (pinfunction "SHIELD_SH4") (pintype "passive"))
      (node (ref "R1_USB") (pin "1") (pinfunction "1_1") (pintype "bidirectional"))
      (node (ref "R2_EP_DR") (pin "1") (pinfunction "1_1") (pintype "bidirectional"))
      (node (ref "R2_USB") (pin "2") (pinfunction "2_2") (pintype "bidirectional"))
      (node (ref "R3") (pin "1") (pinfunction "1_1") (pintype "bidirectional"))
      (node (ref "R9") (pin "1") (pinfunction "1_1") (pintype "bidirectional"))
      (node (ref "R_TYPE_SEL") (pin "1") (pinfunction "1_1") (pintype "bidirectional"))
      (node (ref "SJ1") (pin "1") (pinfunction "1_1") (pintype "passive"))
      (node (ref "SW_DN") (pin "1") (pinfunction "1_1") (pintype "passive"))
      (node (ref "SW_ENT") (pin "1") (pinfunction "1_1") (pintype "passive"))
      (node (ref "SW_UP") (pin "1") (pinfunction "1_1") (pintype "passive"))
      (node (ref "TP_BAT_GND") (pin "TP") (pinfunction "TP_TP") (pintype "input"))
      (node (ref "TP_GND") (pin "TP") (pinfunction "TP_TP") (pintype "input"))
      (node (ref "U1") (pin "P$74") (pinfunction "VSS_PAD_P$74") (pintype "bidirectional"))
      (node (ref "U1") (pin "P$75") (pinfunction "VSS_PAD_P$75") (pintype "bidirectional"))
      (node (ref "U1") (pin "P$76") (pinfunction "VSS_PAD_P$76") (pintype "bidirectional"))
      (node (ref "U1") (pin "P$77") (pinfunction "VSS_PAD_P$77") (pintype "bidirectional"))
      (node (ref "U1") (pin "P$78") (pinfunction "VSS_PAD_P$78") (pintype "bidirectional"))
      (node (ref "U1") (pin "P$79") (pinfunction "VSS_PAD_P$79") (pintype "bidirectional"))
      (node (ref "U1") (pin "P$80") (pinfunction "VSS_PAD_P$80") (pintype "bidirectional"))
      (node (ref "U1") (pin "P$81") (pinfunction "VSS_PAD_P$81") (pintype "bidirectional"))
      (node (ref "U1") (pin "P$82") (pinfunction "VSS_PAD_P$82") (pintype "bidirectional"))
      (node (ref "U1") (pin "P$83") (pinfunction "VSS_PAD_P$83") (pintype "bidirectional"))
      (node (ref "U1") (pin "P$84") (pinfunction "VSS_PAD_P$84") (pintype "bidirectional"))
      (node (ref "U1") (pin "P$85") (pinfunction "VSS_PAD_P$85") (pintype "bidirectional"))
      (node (ref "U1") (pin "P$86") (pinfunction "VSS_PAD_P$86") (pintype "bidirectional"))
      (node (ref "U1") (pin "P$87") (pinfunction "VSS_PAD_P$87") (pintype "bidirectional"))
      (node (ref "U1") (pin "P$88") (pinfunction "VSS_PAD_P$88") (pintype "bidirectional"))
      (node (ref "U1") (pin "P$89") (pinfunction "VSS_PAD_P$89") (pintype "bidirectional"))
      (node (ref "U1") (pin "P$90") (pinfunction "VSS_PAD_P$90") (pintype "bidirectional"))
      (node (ref "U1") (pin "P$B7") (pinfunction "VSS_P$B7") (pintype "power_in"))
      (node (ref "U1") (pin "P$F23") (pinfunction "VSS_PA_P$F23") (pintype "bidirectional"))
      (node (ref "U3") (pin "1") (pinfunction "CTG_1") (pintype "power_in"))
      (node (ref "U3") (pin "4") (pinfunction "GND_4") (pintype "power_in"))
      (node (ref "U3") (pin "6") (pinfunction "QSTRT_6") (pintype "input"))
      (node (ref "U3") (pin "9") (pinfunction "EP_9") (pintype "power_in"))
      (node (ref "X1") (pin "2") (pinfunction "2_2") (pintype "passive"))
      (node (ref "X1") (pin "4") (pinfunction "4_4") (pintype "passive"))
    )
    (net (code "14") (name "HAPTIC_EN") (class "Default")
      (node (ref "IC2") (pin "A1") (pinfunction "EN_A1") (pintype "bidirectional"))
      (node (ref "U1") (pin "P$U1") (pinfunction "P0.12_P$U1") (pintype "bidirectional"))
    )
    (net (code "15") (name "IMU_INT1") (class "Default")
      (node (ref "U1") (pin "P$N1") (pinfunction "P0.08_P$N1") (pintype "bidirectional"))
    )
    (net (code "16") (name "IMU_INT2") (class "Default")
      (node (ref "U1") (pin "P$P2") (pinfunction "P1.08_P$P2") (pintype "bidirectional"))
    )
    (net (code "17") (name "LX1") (class "Default")
      (node (ref "IC9") (pin "B2") (pinfunction "SW1_1_B2") (pintype "bidirectional"))
      (node (ref "IC9") (pin "B3") (pinfunction "SW1_2_B3") (pintype "bidirectional"))
      (node (ref "L7") (pin "1") (pinfunction "1_1") (pintype "bidirectional"))
    )
    (net (code "18") (name "LX2") (class "Default")
      (node (ref "IC9") (pin "D2") (pinfunction "SW2_1_D2") (pintype "bidirectional"))
      (node (ref "IC9") (pin "D3") (pinfunction "SW2_2_D3") (pintype "bidirectional"))
      (node (ref "L7") (pin "2") (pinfunction "2_2") (pintype "bidirectional"))
    )
    (net (code "19") (name "MOSI") (class "Default")
      (node (ref "J1") (pin "14") (pinfunction "14_14") (pintype "bidirectional"))
      (node (ref "U1") (pin "P$B13") (pinfunction "P0.03/AIN1_P$B13") (pintype "bidirectional"))
    )
    (net (code "20") (name "MU_INT1") (class "Default")
      (node (ref "IC3") (pin "5") (pinfunction "INT1_5") (pintype "bidirectional"))
    )
    (net (code "21") (name "MU_INT2") (class "Default")
      (node (ref "IC3") (pin "6") (pinfunction "INT2_6") (pintype "bidirectional"))
    )
    (net (code "22") (name "Net-(ANT1-FEED)") (class "Default")
      (node (ref "ANT1") (pin "1") (pinfunction "FEED_1") (pintype "input"))
      (node (ref "C22") (pin "2") (pinfunction "2_2") (pintype "passive"))
      (node (ref "C4") (pin "2") (pinfunction "2_2") (pintype "passive"))
      (node (ref "L1") (pin "2") (pinfunction "2_2") (pintype "passive"))
    )
    (net (code "23") (name "Net-(D2-K)") (class "Default")
      (node (ref "C2-EP-DR") (pin "1") (pinfunction "1_1") (pintype "passive"))
      (node (ref "D2") (pin "1") (pinfunction "K_1") (pintype "bidirectional"))
      (node (ref "D4") (pin "2") (pinfunction "A_2") (pintype "bidirectional"))
    )
    (net (code "24") (name "Net-(D5-A)") (class "Default")
      (node (ref "C2-EP-DR") (pin "2") (pinfunction "2_2") (pintype "passive"))
      (node (ref "D5") (pin "2") (pinfunction "A_2") (pintype "bidirectional"))
      (node (ref "L5") (pin "1") (pinfunction "1_1") (pintype "passive"))
      (node (ref "Q3") (pin "3") (pinfunction "D_3") (pintype "bidirectional"))
    )
    (net (code "25") (name "Net-(EPD_C1-Pad2)") (class "Default")
      (node (ref "EPD_C1") (pin "2") (pinfunction "2_2") (pintype "passive"))
      (node (ref "J1") (pin "5") (pinfunction "5_5") (pintype "bidirectional"))
    )
    (net (code "26") (name "Net-(EPD_C2-Pad2)") (class "Default")
      (node (ref "EPD_C2") (pin "2") (pinfunction "2_2") (pintype "passive"))
      (node (ref "J1") (pin "4") (pinfunction "4_4") (pintype "bidirectional"))
    )
    (net (code "27") (name "Net-(EPD_C6-Pad2)") (class "Default")
      (node (ref "EPD_C6") (pin "2") (pinfunction "2_2") (pintype "passive"))
      (node (ref "J1") (pin "18") (pinfunction "18_18") (pintype "bidirectional"))
    )
    (net (code "28") (name "Net-(EPD_C7-Pad2)") (class "Default")
      (node (ref "EPD_C7") (pin "2") (pinfunction "2_2") (pintype "passive"))
      (node (ref "J1") (pin "19") (pinfunction "19_19") (pintype "bidirectional"))
    )
    (net (code "29") (name "Net-(EPD_C8-Pad2)") (class "Default")
      (node (ref "EPD_C8") (pin "2") (pinfunction "2_2") (pintype "passive"))
      (node (ref "J1") (pin "20") (pinfunction "20_20") (pintype "bidirectional"))
    )
    (net (code "30") (name "Net-(EPD_C10-Pad2)") (class "Default")
      (node (ref "EPD_C10") (pin "2") (pinfunction "2_2") (pintype "passive"))
      (node (ref "J1") (pin "22") (pinfunction "22_22") (pintype "bidirectional"))
    )
    (net (code "31") (name "Net-(EPD_C12-Pad2)") (class "Default")
      (node (ref "EPD_C12") (pin "2") (pinfunction "2_2") (pintype "passive"))
      (node (ref "J1") (pin "24") (pinfunction "24_24") (pintype "bidirectional"))
    )
    (net (code "32") (name "Net-(IC1-TS{slash}MR)") (class "Default")
      (node (ref "IC1") (pin "D1") (pinfunction "TS/MR_D1") (pintype "bidirectional"))
      (node (ref "R9") (pin "2") (pinfunction "2_2") (pintype "bidirectional"))
    )
    (net (code "33") (name "Net-(IC2-REG)") (class "Default")
      (node (ref "C32") (pin "2") (pinfunction "2_2") (pintype "passive"))
      (node (ref "IC2") (pin "A2") (pinfunction "REG_A2") (pintype "bidirectional"))
    )
    (net (code "34") (name "Net-(IC3-SDO)") (class "Default")
      (node (ref "IC3") (pin "1") (pinfunction "SDO_1") (pintype "bidirectional"))
      (node (ref "R3") (pin "2") (pinfunction "2_2") (pintype "bidirectional"))
    )
    (net (code "35") (name "Net-(IC9-SCL)") (class "Default")
      (node (ref "IC9") (pin "D1") (pinfunction "SCL_D1") (pintype "bidirectional"))
      (node (ref "R4") (pin "2") (pinfunction "2_2") (pintype "bidirectional"))
    )
    (net (code "36") (name "Net-(IC9-SDA)") (class "Default")
      (node (ref "IC9") (pin "E1") (pinfunction "SDA_E1") (pintype "bidirectional"))
      (node (ref "R2") (pin "2") (pinfunction "2_2") (pintype "bidirectional"))
    )
    (net (code "37") (name "Net-(J4-CC1)") (class "Default")
      (node (ref "J4") (pin "A5") (pinfunction "CC1_A5") (pintype "bidirectional"))
      (node (ref "R1_USB") (pin "2") (pinfunction "2_2") (pintype "bidirectional"))
    )
    (net (code "38") (name "Net-(J4-CC2)") (class "Default")
      (node (ref "J4") (pin "B5") (pinfunction "CC2_B5") (pintype "bidirectional"))
      (node (ref "R2_USB") (pin "1") (pinfunction "1_1") (pintype "bidirectional"))
    )
    (net (code "39") (name "Net-(L2-Pad2)") (class "Default")
      (node (ref "L2") (pin "2") (pinfunction "2_2") (pintype "passive"))
      (node (ref "L3") (pin "1") (pinfunction "1_1") (pintype "passive"))
    )
    (net (code "40") (name "Net-(R1_EP_DR-Pad1)") (class "Default")
      (node (ref "R1_EP_DR") (pin "1") (pinfunction "1_1") (pintype "bidirectional"))
      (node (ref "R_TYPE_SEL") (pin "2") (pinfunction "2_2") (pintype "bidirectional"))
      (node (ref "SJ1") (pin "2") (pinfunction "2_2") (pintype "passive"))
    )
    (net (code "41") (name "Net-(U1-ANT)") (class "Default")
      (node (ref "C3") (pin "2") (pinfunction "2_2") (pintype "passive"))
      (node (ref "L1") (pin "1") (pinfunction "1_1") (pintype "passive"))
      (node (ref "U1") (pin "P$H23") (pinfunction "ANT_P$H23") (pintype "bidirectional"))
    )
    (net (code "42") (name "Net-(U1-DCC)") (class "Default")
      (node (ref "L2") (pin "1") (pinfunction "1_1") (pintype "passive"))
      (node (ref "U1") (pin "P$B3") (pinfunction "DCC_P$B3") (pintype "output"))
    )
    (net (code "43") (name "Net-(U1-DEC1)") (class "Default")
      (node (ref "C5") (pin "1") (pinfunction "1_1") (pintype "passive"))
      (node (ref "U1") (pin "P$C1") (pinfunction "DEC1_P$C1") (pintype "power_in"))
    )
    (net (code "44") (name "Net-(U1-DEC2)") (class "Default")
      (node (ref "C13") (pin "2") (pinfunction "2_2") (pintype "passive"))
      (node (ref "U1") (pin "P$A18") (pinfunction "DEC2_P$A18") (pintype "bidirectional"))
    )
    (net (code "45") (name "Net-(U1-DEC3)") (class "Default")
      (node (ref "C11") (pin "2") (pinfunction "2_2") (pintype "passive"))
      (node (ref "U1") (pin "P$D23") (pinfunction "DEC3_P$D23") (pintype "bidirectional"))
    )
    (net (code "46") (name "Net-(U1-DEC3V3)") (class "Default")
      (node (ref "C20") (pin "1") (pinfunction "1_1") (pintype "passive"))
      (node (ref "U1") (pin "P$AC5") (pinfunction "DEC3V3_P$AC5") (pintype "bidirectional"))
    )
    (net (code "47") (name "Net-(U1-DEC4)") (class "Default")
      (node (ref "C10") (pin "2") (pinfunction "2_2") (pintype "passive"))
      (node (ref "C15") (pin "1") (pinfunction "1_1") (pintype "passive"))
      (node (ref "C16") (pin "2") (pinfunction "2_2") (pintype "passive"))
      (node (ref "L3") (pin "2") (pinfunction "2_2") (pintype "passive"))
      (node (ref "U1") (pin "P$B5") (pinfunction "DEC4_P$B5") (pintype "power_in"))
      (node (ref "U1") (pin "P$E24") (pinfunction "DEC6_P$E24") (pintype "bidirectional"))
    )
    (net (code "48") (name "Net-(U1-DEC5)") (class "Default")
      (node (ref "C9") (pin "2") (pinfunction "2_2") (pintype "passive"))
      (node (ref "U1") (pin "P$N24") (pinfunction "DEC5_P$N24") (pintype "bidirectional"))
    )
    (net (code "49") (name "Net-(U1-P0.00{slash}XL1)") (class "Default")
      (node (ref "C17") (pin "2") (pinfunction "2_2") (pintype "passive"))
      (node (ref "U1") (pin "P$D2") (pinfunction "P0.00/XL1_P$D2") (pintype "bidirectional"))
      (node (ref "X2\\") (pin "1") (pinfunction "1_1") (pintype "passive"))
    )
    (net (code "50") (name "Net-(U1-P0.01{slash}XL2)") (class "Default")
      (node (ref "C18") (pin "2") (pinfunction "2_2") (pintype "passive"))
      (node (ref "U1") (pin "P$F2") (pinfunction "P0.01/XL2_P$F2") (pintype "bidirectional"))
      (node (ref "X2\\") (pin "2") (pinfunction "2_2") (pintype "passive"))
    )
    (net (code "51") (name "Net-(U1-XC1)") (class "Default")
      (node (ref "C1") (pin "1") (pinfunction "1_1") (pintype "passive"))
      (node (ref "C2") (pin "1") (pinfunction "1_1") (pintype "passive"))
      (node (ref "U1") (pin "P$B24") (pinfunction "XC1_P$B24") (pintype "input"))
      (node (ref "X1") (pin "1") (pinfunction "1_1") (pintype "passive"))
      (node (ref "X1") (pin "3") (pinfunction "3_3") (pintype "passive"))
    )
    (net (code "52") (name "OUT+") (class "Default")
      (node (ref "IC2") (pin "A3") (pinfunction "OUT+_A3") (pintype "bidirectional"))
      (node (ref "TP_OP") (pin "TP") (pinfunction "TP_TP") (pintype "input"))
    )
    (net (code "53") (name "OUT-") (class "Default")
      (node (ref "IC2") (pin "C3") (pinfunction "OUT-_C3") (pintype "bidirectional"))
      (node (ref "TP_ON") (pin "TP") (pinfunction "TP_TP") (pintype "input"))
    )
    (net (code "54") (name "P0.04") (class "Default")
      (node (ref "U1") (pin "P$J1") (pinfunction "P0.04/AIN2_P$J1") (pintype "bidirectional"))
    )
    (net (code "55") (name "P0.09") (class "Default")
      (node (ref "U1") (pin "P$L24") (pinfunction "P0.09/NFC1_P$L24") (pintype "bidirectional"))
    )
    (net (code "56") (name "P0.13") (class "Default")
      (node (ref "C30") (pin "2") (pinfunction "2_2") (pintype "passive"))
      (node (ref "R5") (pin "1") (pinfunction "1_1") (pintype "bidirectional"))
      (node (ref "SW_UP") (pin "2") (pinfunction "2_2") (pintype "passive"))
      (node (ref "U1") (pin "P$AD8") (pinfunction "P0.13_P$AD8") (pintype "bidirectional"))
    )
    (net (code "57") (name "P0.14") (class "Default")
      (node (ref "C31") (pin "2") (pinfunction "2_2") (pintype "passive"))
      (node (ref "R8") (pin "1") (pinfunction "1_1") (pintype "bidirectional"))
      (node (ref "SW_ENT") (pin "2") (pinfunction "2_2") (pintype "passive"))
      (node (ref "U1") (pin "P$AC9") (pinfunction "P0.14_P$AC9") (pintype "bidirectional"))
    )
    (net (code "58") (name "P0.19") (class "Default")
      (node (ref "U1") (pin "P$AC15") (pinfunction "P0.19_P$AC15") (pintype "bidirectional"))
    )
    (net (code "59") (name "P0.20") (class "Default")
      (node (ref "U1") (pin "P$AD16") (pinfunction "P0.20_P$AD16") (pintype "bidirectional"))
    )
    (net (code "60") (name "P0.21") (class "Default")
      (node (ref "U1") (pin "P$AC17") (pinfunction "P0.21_P$AC17") (pintype "bidirectional"))
    )
    (net (code "61") (name "P0.22") (class "Default")
      (node (ref "U1") (pin "P$AD18") (pinfunction "P0.22_P$AD18") (pintype "bidirectional"))
    )
    (net (code "62") (name "P0.23") (class "Default")
      (node (ref "U1") (pin "P$AC19") (pinfunction "P0.23_P$AC19") (pintype "bidirectional"))
    )
    (net (code "63") (name "P0.24") (class "Default")
      (node (ref "U1") (pin "P$AD20") (pinfunction "P0.24_P$AD20") (pintype "bidirectional"))
    )
    (net (code "64") (name "P0.25") (class "Default")
      (node (ref "U1") (pin "P$AC21") (pinfunction "P0.25_P$AC21") (pintype "bidirectional"))
    )
    (net (code "65") (name "P0.26") (class "Default")
      (node (ref "U1") (pin "P$G1") (pinfunction "P0.26_P$G1") (pintype "bidirectional"))
    )
    (net (code "66") (name "P0.27") (class "Default")
      (node (ref "U1") (pin "P$H2") (pinfunction "P0.27_P$H2") (pintype "bidirectional"))
    )
    (net (code "67") (name "P0.28") (class "Default")
      (node (ref "U1") (pin "P$B11") (pinfunction "P0.28/AIN4_P$B11") (pintype "bidirectional"))
    )
    (net (code "68") (name "P0.29") (class "Default")
      (node (ref "U1") (pin "P$A10") (pinfunction "P0.29/AIN5_P$A10") (pintype "bidirectional"))
    )
    (net (code "69") (name "P0.30") (class "Default")
      (node (ref "U1") (pin "P$B9") (pinfunction "P0.30/AIN6_P$B9") (pintype "bidirectional"))
    )
    (net (code "70") (name "P0.31") (class "Default")
      (node (ref "U1") (pin "P$A8") (pinfunction "P0.31/AIN7_P$A8") (pintype "bidirectional"))
    )
    (net (code "71") (name "P1.01") (class "Default")
      (node (ref "Q1") (pin "1") (pinfunction "G_1") (pintype "bidirectional"))
      (node (ref "R_PWR_EPD") (pin "1") (pinfunction "1_1") (pintype "bidirectional"))
      (node (ref "U1") (pin "P$Y23") (pinfunction "P1.01_P$Y23") (pintype "bidirectional"))
    )
    (net (code "72") (name "P1.02") (class "Default")
      (node (ref "C29") (pin "1") (pinfunction "1_1") (pintype "passive"))
      (node (ref "R7") (pin "1") (pinfunction "1_1") (pintype "bidirectional"))
      (node (ref "SW_DN") (pin "2") (pinfunction "2_2") (pintype "passive"))
      (node (ref "U1") (pin "P$W24") (pinfunction "P1.02_P$W24") (pintype "bidirectional"))
    )
    (net (code "73") (name "P1.03") (class "Default")
      (node (ref "U1") (pin "P$V23") (pinfunction "P1.03_P$V23") (pintype "bidirectional"))
    )
    (net (code "74") (name "P1.04") (class "Default")
      (node (ref "U1") (pin "P$U24") (pinfunction "P1.04_P$U24") (pintype "bidirectional"))
    )
    (net (code "75") (name "P1.05") (class "Default")
      (node (ref "U1") (pin "P$T23") (pinfunction "P1.05_P$T23") (pintype "bidirectional"))
    )
    (net (code "76") (name "P1.06") (class "Default")
      (node (ref "U1") (pin "P$R24") (pinfunction "P1.06_P$R24") (pintype "bidirectional"))
    )
    (net (code "77") (name "P1.07") (class "Default")
      (node (ref "U1") (pin "P$P23") (pinfunction "P1.07_P$P23") (pintype "bidirectional"))
    )
    (net (code "78") (name "P1.09") (class "Default")
      (node (ref "U1") (pin "P$R1") (pinfunction "P1.09_P$R1") (pintype "bidirectional"))
    )
    (net (code "79") (name "P1.10") (class "Default")
      (node (ref "U1") (pin "P$A20") (pinfunction "P1.10_P$A20") (pintype "bidirectional"))
    )
    (net (code "80") (name "P1.11") (class "Default")
      (node (ref "U1") (pin "P$B19") (pinfunction "P1.11_P$B19") (pintype "bidirectional"))
    )
    (net (code "81") (name "P1.12") (class "Default")
      (node (ref "U1") (pin "P$B17") (pinfunction "P1.12_P$B17") (pintype "bidirectional"))
    )
    (net (code "82") (name "P1.13") (class "Default")
      (node (ref "U1") (pin "P$A16") (pinfunction "P1.13_P$A16") (pintype "bidirectional"))
    )
    (net (code "83") (name "P1.14") (class "Default")
      (node (ref "U1") (pin "P$B15") (pinfunction "P1.14_P$B15") (pintype "bidirectional"))
    )
    (net (code "84") (name "P1.15") (class "Default")
      (node (ref "U1") (pin "P$A14") (pinfunction "P1.15_P$A14") (pintype "bidirectional"))
    )
    (net (code "85") (name "PMIC_IN") (class "Default")
      (node (ref "IC1") (pin "A1") (pinfunction "~{INT}_A1") (pintype "bidirectional"))
    )
    (net (code "86") (name "PMIC_INT") (class "Default")
      (node (ref "U1") (pin "P$T2") (pinfunction "P0.11_P$T2") (pintype "bidirectional"))
    )
    (net (code "87") (name "PREVGH") (class "Default")
      (node (ref "D5") (pin "1") (pinfunction "K_1") (pintype "bidirectional"))
      (node (ref "EPD_C9") (pin "2") (pinfunction "2_2") (pintype "passive"))
      (node (ref "J1") (pin "21") (pinfunction "21_21") (pintype "bidirectional"))
    )
    (net (code "88") (name "PREVGL") (class "Default")
      (node (ref "D2") (pin "2") (pinfunction "A_2") (pintype "bidirectional"))
      (node (ref "EPD_C11") (pin "2") (pinfunction "2_2") (pintype "passive"))
      (node (ref "J1") (pin "23") (pinfunction "23_23") (pintype "bidirectional"))
    )
    (net (code "89") (name "RESE") (class "Default")
      (node (ref "J1") (pin "3") (pinfunction "3_3") (pintype "bidirectional"))
      (node (ref "Q3") (pin "2") (pinfunction "S_2") (pintype "bidirectional"))
      (node (ref "R1_EP_DR") (pin "2") (pinfunction "2_2") (pintype "bidirectional"))
    )
    (net (code "90") (name "RESET") (class "Default")
      (node (ref "J2") (pin "6") (pinfunction "6_6") (pintype "bidirectional"))
      (node (ref "TP_RESET") (pin "TP") (pinfunction "TP_TP") (pintype "input"))
      (node (ref "U1") (pin "P$AC13") (pinfunction "P0.18/RESET_P$AC13") (pintype "bidirectional"))
    )
    (net (code "91") (name "SCK") (class "Default")
      (node (ref "J1") (pin "13") (pinfunction "13_13") (pintype "bidirectional"))
      (node (ref "U1") (pin "P$A12") (pinfunction "P0.02/AIN0_P$A12") (pintype "bidirectional"))
    )
    (net (code "92") (name "SCL") (class "Default")
      (node (ref "IC1") (pin "B1") (pinfunction "SCL_B1") (pintype "bidirectional"))
      (node (ref "IC2") (pin "C1") (pinfunction "SCL_C1") (pintype "bidirectional"))
      (node (ref "IC3") (pin "12") (pinfunction "SCX_12") (pintype "bidirectional"))
      (node (ref "R17") (pin "2") (pinfunction "2_2") (pintype "bidirectional"))
      (node (ref "R4") (pin "1") (pinfunction "1_1") (pintype "bidirectional"))
      (node (ref "TP_SCL") (pin "TP") (pinfunction "TP_TP") (pintype "input"))
      (node (ref "U1") (pin "P$M2") (pinfunction "P0.07_P$M2") (pintype "bidirectional"))
      (node (ref "U3") (pin "7") (pinfunction "SCL_7") (pintype "input"))
    )
    (net (code "93") (name "SDA") (class "Default")
      (node (ref "IC1") (pin "C1") (pinfunction "SDA_C1") (pintype "bidirectional"))
      (node (ref "IC2") (pin "B2") (pinfunction "SDA_B2") (pintype "bidirectional"))
      (node (ref "IC3") (pin "2") (pinfunction "SDX_2") (pintype "bidirectional"))
      (node (ref "R18") (pin "2") (pinfunction "2_2") (pintype "bidirectional"))
      (node (ref "R2") (pin "1") (pinfunction "1_1") (pintype "bidirectional"))
      (node (ref "TP_SDA") (pin "TP") (pinfunction "TP_TP") (pintype "input"))
      (node (ref "U1") (pin "P$L1") (pinfunction "P0.06_P$L1") (pintype "bidirectional"))
      (node (ref "U3") (pin "8") (pinfunction "SDA_8") (pintype "bidirectional"))
    )
    (net (code "94") (name "SWDCLK") (class "Default")
      (node (ref "J2") (pin "4") (pinfunction "4_4") (pintype "bidirectional"))
      (node (ref "TP_SWDCLK") (pin "TP") (pinfunction "TP_TP") (pintype "input"))
      (node (ref "U1") (pin "P$AA24") (pinfunction "SWDCLK_P$AA24") (pintype "input"))
    )
    (net (code "95") (name "SWDIO") (class "Default")
      (node (ref "J2") (pin "2") (pinfunction "2_2") (pintype "bidirectional"))
      (node (ref "TP_SWDIO") (pin "TP") (pinfunction "TP_TP") (pintype "input"))
      (node (ref "U1") (pin "P$AC24") (pinfunction "SWDIO_P$AC24") (pintype "bidirectional"))
    )
    (net (code "96") (name "SWO") (class "Default")
      (node (ref "TP_SWO") (pin "TP") (pinfunction "TP_TP") (pintype "input"))
      (node (ref "U1") (pin "P$AD22") (pinfunction "P1.00_P$AD22") (pintype "bidirectional"))
    )
    (net (code "97") (name "VBAT") (class "Default")
      (node (ref "C27") (pin "2") (pinfunction "2_2") (pintype "passive"))
      (node (ref "C37") (pin "1") (pinfunction "1_1") (pintype "passive"))
      (node (ref "IC1") (pin "C2") (pinfunction "BAT_C2") (pintype "bidirectional"))
      (node (ref "TP_VBAT") (pin "TP") (pinfunction "TP_TP") (pintype "input"))
      (node (ref "U3") (pin "2") (pinfunction "CELL_2") (pintype "power_in"))
      (node (ref "U3") (pin "3") (pinfunction "VDD_3") (pintype "power_in"))
    )
    (net (code "98") (name "VBUS") (class "Default")
      (node (ref "C21") (pin "1") (pinfunction "1_1") (pintype "passive"))
      (node (ref "C38") (pin "1") (pinfunction "1_1") (pintype "passive"))
      (node (ref "C42") (pin "1") (pinfunction "1_1") (pintype "passive"))
      (node (ref "C43") (pin "1") (pinfunction "1_1") (pintype "passive"))
      (node (ref "D3") (pin "5") (pinfunction "VBUS_5") (pintype "bidirectional"))
      (node (ref "IC1") (pin "A2") (pinfunction "IN_A2") (pintype "bidirectional"))
      (node (ref "J4") (pin "A4_B9") (pinfunction "VBUS_A4_B9") (pintype "power_in"))
      (node (ref "J4") (pin "A9_B4") (pinfunction "VBUS_A9_B4") (pintype "power_in"))
      (node (ref "U1") (pin "P$AD2") (pinfunction "VBUS_P$AD2") (pintype "power_in"))
    )
    (net (code "99") (name "VREG") (class "Default")
      (node (ref "C23") (pin "2") (pinfunction "2_2") (pintype "passive"))
      (node (ref "C24") (pin "2") (pinfunction "2_2") (pintype "passive"))
      (node (ref "C39") (pin "1") (pinfunction "1_1") (pintype "passive"))
      (node (ref "IC1") (pin "B2") (pinfunction "SYS_B2") (pintype "bidirectional"))
      (node (ref "IC9") (pin "A1") (pinfunction "EN_A1") (pintype "bidirectional"))
      (node (ref "IC9") (pin "A2") (pinfunction "VIN_1_A2") (pintype "bidirectional"))
      (node (ref "IC9") (pin "A3") (pinfunction "VIN_2_A3") (pintype "bidirectional"))
      (node (ref "TP_VREG") (pin "TP") (pinfunction "TP_TP") (pintype "input"))
    )
    (net (code "100") (name "unconnected-(ANT1-NC-Pad2)") (class "Default")
      (node (ref "ANT1") (pin "2") (pinfunction "NC_2") (pintype "no_connect"))
    )
    (net (code "101") (name "unconnected-(IC3-ASCL-Pad11)") (class "Default")
      (node (ref "IC3") (pin "11") (pinfunction "ASCL_11") (pintype "bidirectional"))
    )
    (net (code "102") (name "unconnected-(IC3-ASDA-Pad4)") (class "Default")
      (node (ref "IC3") (pin "4") (pinfunction "ASDA_4") (pintype "bidirectional"))
    )
    (net (code "103") (name "unconnected-(J1-Pad1)") (class "Default")
      (node (ref "J1") (pin "1") (pinfunction "1_1") (pintype "bidirectional"))
    )
    (net (code "104") (name "unconnected-(J1-Pad6)") (class "Default")
      (node (ref "J1") (pin "6") (pinfunction "6_6") (pintype "bidirectional"))
    )
    (net (code "105") (name "unconnected-(J1-Pad7)") (class "Default")
      (node (ref "J1") (pin "7") (pinfunction "7_7") (pintype "bidirectional"))
    )
    (net (code "106") (name "unconnected-(J4-SBU1-PadA8)") (class "Default")
      (node (ref "J4") (pin "A8") (pinfunction "SBU1_A8") (pintype "bidirectional"))
    )
    (net (code "107") (name "unconnected-(J4-SBU2-PadB8)") (class "Default")
      (node (ref "J4") (pin "B8") (pinfunction "SBU2_B8") (pintype "bidirectional"))
    )
    (net (code "108") (name "unconnected-(U1-DCCH-PadP$AB2)") (class "Default")
      (node (ref "U1") (pin "P$AB2") (pinfunction "DCCH_P$AB2") (pintype "bidirectional"))
    )
    (net (code "109") (name "unconnected-(U1-XC2-PadP$A23)") (class "Default")
      (node (ref "U1") (pin "P$A23") (pinfunction "XC2_P$A23") (pintype "output"))
    )
  )
)
